# SwBotMain.net
KiCad netlist of a schematic drawn in EAGLE
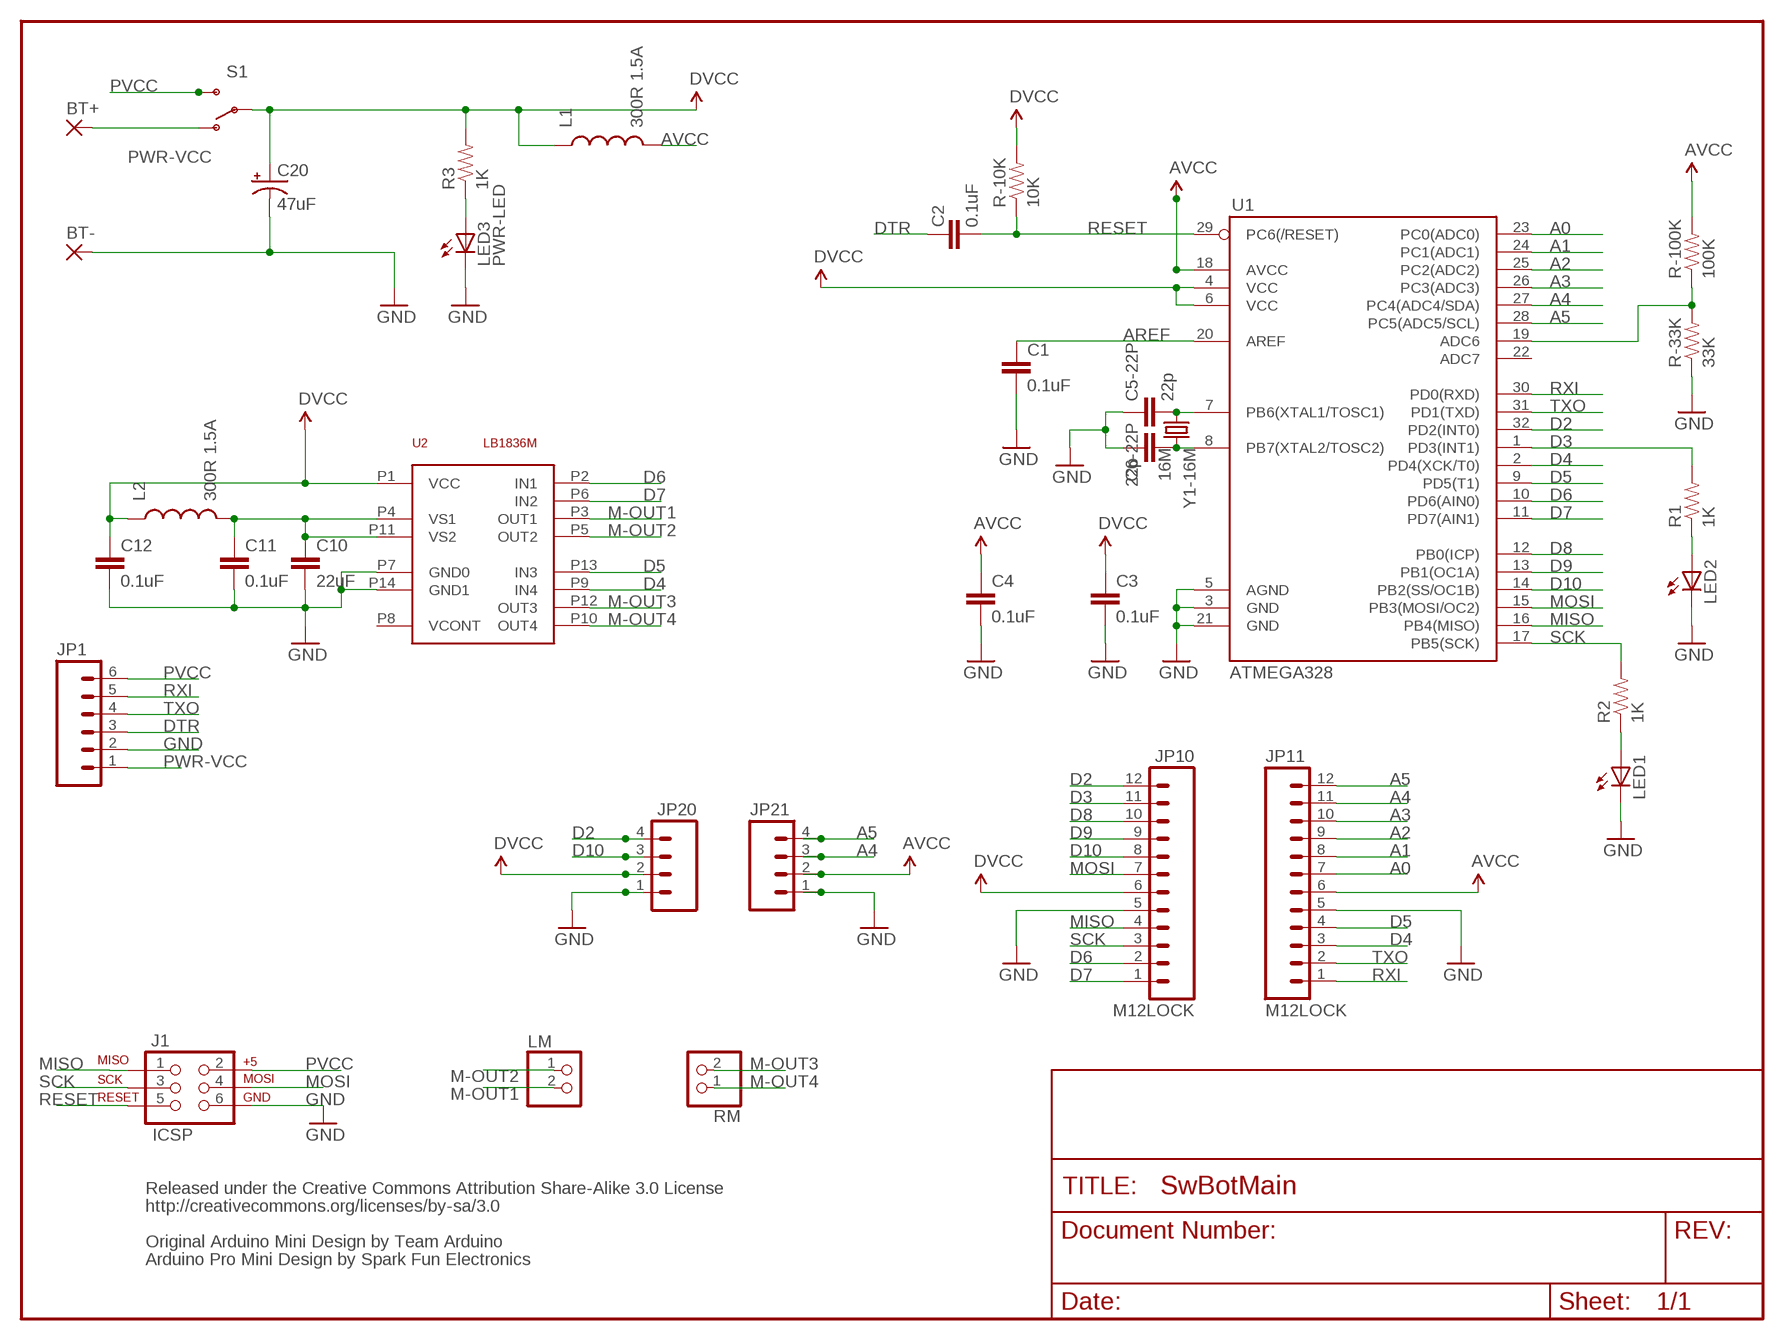
[diagram p0: schematic, sheet 1]

(export (version "E")
  (design (tool "Eeschema 10.0.6"))
  (components
    (comp (ref "BT+")
      (value "SMD2")
      (footprint "eagle-import:SMD1,27-2,54")
      (libsource (lib "eagle-import") (part "SMD2"))
    )
    (comp (ref "BT-")
      (value "SMD2")
      (footprint "eagle-import:SMD1,27-2,54")
      (libsource (lib "eagle-import") (part "SMD2"))
    )
    (comp (ref "C1")
      (value "0.1uF")
      (footprint "eagle-import:0805")
      (libsource (lib "eagle-import") (part "SparkFun-Capacitors_CAP0805"))
    )
    (comp (ref "C2")
      (value "0.1uF")
      (footprint "eagle-import:0805")
      (libsource (lib "eagle-import") (part "CAP0805"))
    )
    (comp (ref "C3")
      (value "0.1uF")
      (footprint "eagle-import:0805")
      (libsource (lib "eagle-import") (part "SparkFun-Capacitors_CAP0805"))
    )
    (comp (ref "C4")
      (value "0.1uF")
      (footprint "eagle-import:0805")
      (libsource (lib "eagle-import") (part "SparkFun-Capacitors_CAP0805"))
    )
    (comp (ref "C5-22P")
      (value "22p")
      (footprint "eagle-import:0805")
      (libsource (lib "eagle-import") (part "SparkFun-Capacitors_CAP0805"))
    )
    (comp (ref "C6-22P")
      (value "22p")
      (footprint "eagle-import:0805")
      (libsource (lib "eagle-import") (part "SparkFun-Capacitors_CAP0805"))
    )
    (comp (ref "C10")
      (value "22uF")
      (footprint "eagle-import:1206")
      (libsource (lib "eagle-import") (part "CAP1206"))
    )
    (comp (ref "C11")
      (value "0.1uF")
      (footprint "eagle-import:0805")
      (libsource (lib "eagle-import") (part "SparkFun-Capacitors_CAP0805"))
    )
    (comp (ref "C12")
      (value "0.1uF")
      (footprint "eagle-import:0805")
      (libsource (lib "eagle-import") (part "SparkFun-Capacitors_CAP0805"))
    )
    (comp (ref "C20")
      (value "47uF")
      (footprint "eagle-import:EIA3528")
      (libsource (lib "eagle-import") (part "47UF-TANT"))
    )
    (comp (ref "J1")
      (value "ICSP")
      (footprint "eagle-import:2X3_LOCK")
      (libsource (lib "eagle-import") (part "AVR_SPI_PRG_62X3_LOCK"))
    )
    (comp (ref "JP1")
      (value "M06LOCK")
      (footprint "eagle-import:1X06_LOCK")
      (libsource (lib "eagle-import") (part "M06LOCK"))
    )
    (comp (ref "JP10")
      (value "M12LOCK")
      (footprint "eagle-import:1X12_LOCK")
      (libsource (lib "eagle-import") (part "M12LOCK"))
    )
    (comp (ref "JP11")
      (value "M12LOCK")
      (footprint "eagle-import:1X12_LOCK")
      (libsource (lib "eagle-import") (part "M12LOCK"))
    )
    (comp (ref "JP20")
      (value "M04LOCK_LONGPADS")
      (footprint "eagle-import:1X04_LOCK_LONGPADS")
      (libsource (lib "eagle-import") (part "M04LOCK_LONGPADS"))
    )
    (comp (ref "JP21")
      (value "M04LOCK_LONGPADS")
      (footprint "eagle-import:1X04_LOCK_LONGPADS")
      (libsource (lib "eagle-import") (part "M04LOCK_LONGPADS"))
    )
    (comp (ref "L1")
      (value "300R 1.5A")
      (footprint "eagle-import:0805")
      (libsource (lib "eagle-import") (part "INDUCTOR0805"))
    )
    (comp (ref "L2")
      (value "300R 1.5A")
      (footprint "eagle-import:0805")
      (libsource (lib "eagle-import") (part "INDUCTOR0805"))
    )
    (comp (ref "LED1")
      (value "LEDCHIP-LED0805")
      (footprint "eagle-import:CHIP-LED0805")
      (libsource (lib "eagle-import") (part "LEDCHIP-LED0805"))
    )
    (comp (ref "LED2")
      (value "LEDCHIP-LED0805")
      (footprint "eagle-import:CHIP-LED0805")
      (libsource (lib "eagle-import") (part "LEDCHIP-LED0805"))
    )
    (comp (ref "LED3")
      (value "PWR-LED")
      (footprint "eagle-import:LED5MM")
      (libsource (lib "eagle-import") (part "LED5MM"))
    )
    (comp (ref "LM")
      (value "PINHD-1X2")
      (footprint "eagle-import:1X02")
      (libsource (lib "eagle-import") (part "PINHD-1X2"))
    )
    (comp (ref "R-10K")
      (value "10K")
      (footprint "eagle-import:0805")
      (libsource (lib "eagle-import") (part "RESISTOR0805-RES"))
    )
    (comp (ref "R-33K")
      (value "33K")
      (footprint "eagle-import:0805")
      (libsource (lib "eagle-import") (part "RESISTOR0805-RES"))
    )
    (comp (ref "R-100K")
      (value "100K")
      (footprint "eagle-import:0805")
      (libsource (lib "eagle-import") (part "RESISTOR0805-RES"))
    )
    (comp (ref "R1")
      (value "1K")
      (footprint "eagle-import:0805")
      (libsource (lib "eagle-import") (part "RESISTOR0805-RES"))
    )
    (comp (ref "R2")
      (value "1K")
      (footprint "eagle-import:0805")
      (libsource (lib "eagle-import") (part "RESISTOR0805-RES"))
    )
    (comp (ref "R3")
      (value "1K")
      (footprint "eagle-import:0805")
      (libsource (lib "eagle-import") (part "RESISTOR0805-RES"))
    )
    (comp (ref "RM")
      (value "PINHD-1X2")
      (footprint "eagle-import:1X02")
      (libsource (lib "eagle-import") (part "PINHD-1X2"))
    )
    (comp (ref "S1")
      (value "SWITCH-SPDTPTH_LOCK")
      (footprint "eagle-import:SWITCH-SPDT_LOCK.007S")
      (libsource (lib "eagle-import") (part "SWITCH-SPDTPTH_LOCK"))
    )
    (comp (ref "U1")
      (value "ATMEGA328")
      (footprint "eagle-import:TQFP32-08")
      (libsource (lib "eagle-import") (part "ATMEGA168"))
    )
    (comp (ref "U2")
      (value "LB1836M")
      (footprint "eagle-import:MFP14S")
      (libsource (lib "eagle-import") (part "LB1836M"))
    )
    (comp (ref "Y1-16M")
      (value "16M")
      (footprint "eagle-import:CRYSTAL-TXC-7A")
      (libsource (lib "eagle-import") (part "CRYSTALTXC-7A"))
    )
  )
  (nets
    (net (code "1") (name "/A0") (class "Default")
      (node (ref "JP11") (pin "7") (pinfunction "7_7") (pintype "passive"))
      (node (ref "U1") (pin "23") (pinfunction "PC0(ADC0)_23") (pintype "bidirectional"))
    )
    (net (code "2") (name "/A1") (class "Default")
      (node (ref "JP11") (pin "8") (pinfunction "8_8") (pintype "passive"))
      (node (ref "U1") (pin "24") (pinfunction "PC1(ADC1)_24") (pintype "bidirectional"))
    )
    (net (code "3") (name "/A2") (class "Default")
      (node (ref "JP11") (pin "9") (pinfunction "9_9") (pintype "passive"))
      (node (ref "U1") (pin "25") (pinfunction "PC2(ADC2)_25") (pintype "bidirectional"))
    )
    (net (code "4") (name "/A3") (class "Default")
      (node (ref "JP11") (pin "10") (pinfunction "10_10") (pintype "passive"))
      (node (ref "U1") (pin "26") (pinfunction "PC3(ADC3)_26") (pintype "bidirectional"))
    )
    (net (code "5") (name "/A4") (class "Default")
      (node (ref "JP11") (pin "11") (pinfunction "11_11") (pintype "passive"))
      (node (ref "JP21") (pin "3") (pinfunction "3_3") (pintype "passive"))
      (node (ref "U1") (pin "27") (pinfunction "PC4(ADC4/SDA)_27") (pintype "bidirectional"))
    )
    (net (code "6") (name "/A5") (class "Default")
      (node (ref "JP11") (pin "12") (pinfunction "12_12") (pintype "passive"))
      (node (ref "JP21") (pin "4") (pinfunction "4_4") (pintype "passive"))
      (node (ref "U1") (pin "28") (pinfunction "PC5(ADC5/SCL)_28") (pintype "bidirectional"))
    )
    (net (code "7") (name "/AREF") (class "Default")
      (node (ref "C1") (pin "1") (pinfunction "1_1") (pintype "passive"))
      (node (ref "U1") (pin "20") (pinfunction "AREF_20") (pintype "bidirectional"))
    )
    (net (code "8") (name "/D2") (class "Default")
      (node (ref "JP10") (pin "12") (pinfunction "12_12") (pintype "passive"))
      (node (ref "JP20") (pin "4") (pinfunction "4_4") (pintype "passive"))
      (node (ref "U1") (pin "32") (pinfunction "PD2(INT0)_32") (pintype "bidirectional"))
    )
    (net (code "9") (name "/D3") (class "Default")
      (node (ref "JP10") (pin "11") (pinfunction "11_11") (pintype "passive"))
      (node (ref "R1") (pin "2") (pinfunction "2_2") (pintype "passive"))
      (node (ref "U1") (pin "1") (pinfunction "PD3(INT1)_1") (pintype "bidirectional"))
    )
    (net (code "10") (name "/D4") (class "Default")
      (node (ref "JP11") (pin "3") (pinfunction "3_3") (pintype "passive"))
      (node (ref "U1") (pin "2") (pinfunction "PD4(XCK/T0)_2") (pintype "bidirectional"))
      (node (ref "U2") (pin "P9") (pinfunction "IN4_P9") (pintype "input"))
    )
    (net (code "11") (name "/D5") (class "Default")
      (node (ref "JP11") (pin "4") (pinfunction "4_4") (pintype "passive"))
      (node (ref "U1") (pin "9") (pinfunction "PD5(T1)_9") (pintype "bidirectional"))
      (node (ref "U2") (pin "P13") (pinfunction "IN3_P13") (pintype "input"))
    )
    (net (code "12") (name "/D6") (class "Default")
      (node (ref "JP10") (pin "2") (pinfunction "2_2") (pintype "passive"))
      (node (ref "U1") (pin "10") (pinfunction "PD6(AIN0)_10") (pintype "bidirectional"))
      (node (ref "U2") (pin "P2") (pinfunction "IN1_P2") (pintype "input"))
    )
    (net (code "13") (name "/D7") (class "Default")
      (node (ref "JP10") (pin "1") (pinfunction "1_1") (pintype "passive"))
      (node (ref "U1") (pin "11") (pinfunction "PD7(AIN1)_11") (pintype "bidirectional"))
      (node (ref "U2") (pin "P6") (pinfunction "IN2_P6") (pintype "input"))
    )
    (net (code "14") (name "/D8") (class "Default")
      (node (ref "JP10") (pin "10") (pinfunction "10_10") (pintype "passive"))
      (node (ref "U1") (pin "12") (pinfunction "PB0(ICP)_12") (pintype "bidirectional"))
    )
    (net (code "15") (name "/D9") (class "Default")
      (node (ref "JP10") (pin "9") (pinfunction "9_9") (pintype "passive"))
      (node (ref "U1") (pin "13") (pinfunction "PB1(OC1A)_13") (pintype "bidirectional"))
    )
    (net (code "16") (name "/D10") (class "Default")
      (node (ref "JP10") (pin "8") (pinfunction "8_8") (pintype "passive"))
      (node (ref "JP20") (pin "3") (pinfunction "3_3") (pintype "passive"))
      (node (ref "U1") (pin "14") (pinfunction "PB2(SS/OC1B)_14") (pintype "bidirectional"))
    )
    (net (code "17") (name "/DTR") (class "Default")
      (node (ref "C2") (pin "2") (pinfunction "2_2") (pintype "passive"))
      (node (ref "JP1") (pin "3") (pinfunction "3_3") (pintype "passive"))
    )
    (net (code "18") (name "/M-OUT1") (class "Default")
      (node (ref "LM") (pin "2") (pinfunction "2_2") (pintype "passive"))
      (node (ref "U2") (pin "P3") (pinfunction "OUT1_P3") (pintype "output"))
    )
    (net (code "19") (name "/M-OUT2") (class "Default")
      (node (ref "LM") (pin "1") (pinfunction "1_1") (pintype "passive"))
      (node (ref "U2") (pin "P5") (pinfunction "OUT2_P5") (pintype "output"))
    )
    (net (code "20") (name "/M-OUT3") (class "Default")
      (node (ref "RM") (pin "2") (pinfunction "2_2") (pintype "passive"))
      (node (ref "U2") (pin "P12") (pinfunction "OUT3_P12") (pintype "output"))
    )
    (net (code "21") (name "/M-OUT4") (class "Default")
      (node (ref "RM") (pin "1") (pinfunction "1_1") (pintype "passive"))
      (node (ref "U2") (pin "P10") (pinfunction "OUT4_P10") (pintype "output"))
    )
    (net (code "22") (name "/MISO") (class "Default")
      (node (ref "J1") (pin "1") (pinfunction "1_1") (pintype "passive"))
      (node (ref "JP10") (pin "4") (pinfunction "4_4") (pintype "passive"))
      (node (ref "U1") (pin "16") (pinfunction "PB4(MISO)_16") (pintype "bidirectional"))
    )
    (net (code "23") (name "/MOSI") (class "Default")
      (node (ref "J1") (pin "4") (pinfunction "4_4") (pintype "passive"))
      (node (ref "JP10") (pin "7") (pinfunction "7_7") (pintype "passive"))
      (node (ref "U1") (pin "15") (pinfunction "PB3(MOSI/OC2)_15") (pintype "bidirectional"))
    )
    (net (code "24") (name "/PVCC") (class "Default")
      (node (ref "J1") (pin "2") (pinfunction "2_2") (pintype "passive"))
      (node (ref "JP1") (pin "6") (pinfunction "6_6") (pintype "passive"))
      (node (ref "S1") (pin "3") (pinfunction "S_3") (pintype "passive"))
    )
    (net (code "25") (name "/PWR-VCC") (class "Default")
      (node (ref "BT+") (pin "1") (pinfunction "P_1") (pintype "passive"))
      (node (ref "JP1") (pin "1") (pinfunction "1_1") (pintype "passive"))
      (node (ref "S1") (pin "1") (pinfunction "O_1") (pintype "passive"))
    )
    (net (code "26") (name "/RESET") (class "Default")
      (node (ref "C2") (pin "1") (pinfunction "1_1") (pintype "passive"))
      (node (ref "J1") (pin "5") (pinfunction "5_5") (pintype "passive"))
      (node (ref "R-10K") (pin "1") (pinfunction "1_1") (pintype "passive"))
      (node (ref "U1") (pin "29") (pinfunction "PC6(/RESET)_29") (pintype "bidirectional"))
    )
    (net (code "27") (name "/RXI") (class "Default")
      (node (ref "JP1") (pin "5") (pinfunction "5_5") (pintype "passive"))
      (node (ref "JP11") (pin "1") (pinfunction "1_1") (pintype "passive"))
      (node (ref "U1") (pin "30") (pinfunction "PD0(RXD)_30") (pintype "bidirectional"))
    )
    (net (code "28") (name "/SCK") (class "Default")
      (node (ref "J1") (pin "3") (pinfunction "3_3") (pintype "passive"))
      (node (ref "JP10") (pin "3") (pinfunction "3_3") (pintype "passive"))
      (node (ref "R2") (pin "2") (pinfunction "2_2") (pintype "passive"))
      (node (ref "U1") (pin "17") (pinfunction "PB5(SCK)_17") (pintype "bidirectional"))
    )
    (net (code "29") (name "/TXO") (class "Default")
      (node (ref "JP1") (pin "4") (pinfunction "4_4") (pintype "passive"))
      (node (ref "JP11") (pin "2") (pinfunction "2_2") (pintype "passive"))
      (node (ref "U1") (pin "31") (pinfunction "PD1(TXD)_31") (pintype "bidirectional"))
    )
    (net (code "30") (name "AVCC") (class "Default")
      (node (ref "C4") (pin "1") (pinfunction "1_1") (pintype "passive"))
      (node (ref "JP11") (pin "6") (pinfunction "6_6") (pintype "passive"))
      (node (ref "JP21") (pin "2") (pinfunction "2_2") (pintype "passive"))
      (node (ref "L1") (pin "2") (pinfunction "2_2") (pintype "passive"))
      (node (ref "R-100K") (pin "2") (pinfunction "2_2") (pintype "passive"))
      (node (ref "U1") (pin "18") (pinfunction "AVCC_18") (pintype "bidirectional"))
    )
    (net (code "31") (name "DVCC") (class "Default")
      (node (ref "C12") (pin "1") (pinfunction "1_1") (pintype "passive"))
      (node (ref "C20") (pin "A") (pinfunction "+_A") (pintype "passive"))
      (node (ref "C3") (pin "1") (pinfunction "1_1") (pintype "passive"))
      (node (ref "JP10") (pin "6") (pinfunction "6_6") (pintype "passive"))
      (node (ref "JP20") (pin "2") (pinfunction "2_2") (pintype "passive"))
      (node (ref "L1") (pin "1") (pinfunction "1_1") (pintype "passive"))
      (node (ref "L2") (pin "1") (pinfunction "1_1") (pintype "passive"))
      (node (ref "R-10K") (pin "2") (pinfunction "2_2") (pintype "passive"))
      (node (ref "R3") (pin "2") (pinfunction "2_2") (pintype "passive"))
      (node (ref "S1") (pin "2") (pinfunction "P_2") (pintype "passive"))
      (node (ref "U1") (pin "4") (pinfunction "VCC_4") (pintype "bidirectional"))
      (node (ref "U1") (pin "6") (pinfunction "VCC_6") (pintype "bidirectional"))
      (node (ref "U2") (pin "P1") (pinfunction "VCC_P1") (pintype "power_in"))
    )
    (net (code "32") (name "GND") (class "Default")
      (node (ref "BT-") (pin "1") (pinfunction "P_1") (pintype "passive"))
      (node (ref "C1") (pin "2") (pinfunction "2_2") (pintype "passive"))
      (node (ref "C10") (pin "2") (pinfunction "2_2") (pintype "passive"))
      (node (ref "C11") (pin "2") (pinfunction "2_2") (pintype "passive"))
      (node (ref "C12") (pin "2") (pinfunction "2_2") (pintype "passive"))
      (node (ref "C20") (pin "C") (pinfunction "-_C") (pintype "passive"))
      (node (ref "C3") (pin "2") (pinfunction "2_2") (pintype "passive"))
      (node (ref "C4") (pin "2") (pinfunction "2_2") (pintype "passive"))
      (node (ref "C5-22P") (pin "1") (pinfunction "1_1") (pintype "passive"))
      (node (ref "C6-22P") (pin "2") (pinfunction "2_2") (pintype "passive"))
      (node (ref "J1") (pin "6") (pinfunction "6_6") (pintype "passive"))
      (node (ref "JP1") (pin "2") (pinfunction "2_2") (pintype "passive"))
      (node (ref "JP10") (pin "5") (pinfunction "5_5") (pintype "passive"))
      (node (ref "JP11") (pin "5") (pinfunction "5_5") (pintype "passive"))
      (node (ref "JP20") (pin "1") (pinfunction "1_1") (pintype "passive"))
      (node (ref "JP21") (pin "1") (pinfunction "1_1") (pintype "passive"))
      (node (ref "LED1") (pin "C") (pinfunction "C_C") (pintype "passive"))
      (node (ref "LED2") (pin "C") (pinfunction "C_C") (pintype "passive"))
      (node (ref "LED3") (pin "K") (pinfunction "C_K") (pintype "passive"))
      (node (ref "R-33K") (pin "1") (pinfunction "1_1") (pintype "passive"))
      (node (ref "U1") (pin "21") (pinfunction "GND_21") (pintype "bidirectional"))
      (node (ref "U1") (pin "3") (pinfunction "GND_3") (pintype "bidirectional"))
      (node (ref "U1") (pin "5") (pinfunction "AGND_5") (pintype "bidirectional"))
      (node (ref "U2") (pin "P14") (pinfunction "GND1_P14") (pintype "power_in"))
      (node (ref "U2") (pin "P7") (pinfunction "GND0_P7") (pintype "power_in"))
    )
    (net (code "33") (name "Net-(LED1-PadA)") (class "Default")
      (node (ref "LED1") (pin "A") (pinfunction "A_A") (pintype "passive"))
      (node (ref "R2") (pin "1") (pinfunction "1_1") (pintype "passive"))
    )
    (net (code "34") (name "Net-(LED2-PadA)") (class "Default")
      (node (ref "LED2") (pin "A") (pinfunction "A_A") (pintype "passive"))
      (node (ref "R1") (pin "1") (pinfunction "1_1") (pintype "passive"))
    )
    (net (code "35") (name "Net-(LED3-PadA)") (class "Default")
      (node (ref "LED3") (pin "A") (pinfunction "A_A") (pintype "passive"))
      (node (ref "R3") (pin "1") (pinfunction "1_1") (pintype "passive"))
    )
    (net (code "36") (name "Net-(U1-ADC6)") (class "Default")
      (node (ref "R-100K") (pin "1") (pinfunction "1_1") (pintype "passive"))
      (node (ref "R-33K") (pin "2") (pinfunction "2_2") (pintype "passive"))
      (node (ref "U1") (pin "19") (pinfunction "ADC6_19") (pintype "bidirectional"))
    )
    (net (code "37") (name "Net-(U1-PB6(XTAL1{slash}TOSC1))") (class "Default")
      (node (ref "C5-22P") (pin "2") (pinfunction "2_2") (pintype "passive"))
      (node (ref "U1") (pin "7") (pinfunction "PB6(XTAL1/TOSC1)_7") (pintype "bidirectional"))
      (node (ref "Y1-16M") (pin "P$1") (pinfunction "1_P$1") (pintype "passive"))
    )
    (net (code "38") (name "Net-(U1-PB7(XTAL2{slash}TOSC2))") (class "Default")
      (node (ref "C6-22P") (pin "1") (pinfunction "1_1") (pintype "passive"))
      (node (ref "U1") (pin "8") (pinfunction "PB7(XTAL2/TOSC2)_8") (pintype "bidirectional"))
      (node (ref "Y1-16M") (pin "P$2") (pinfunction "2_P$2") (pintype "passive"))
    )
    (net (code "39") (name "Net-(U2-VS1)") (class "Default")
      (node (ref "C10") (pin "1") (pinfunction "1_1") (pintype "passive"))
      (node (ref "C11") (pin "1") (pinfunction "1_1") (pintype "passive"))
      (node (ref "L2") (pin "2") (pinfunction "2_2") (pintype "passive"))
      (node (ref "U2") (pin "P11") (pinfunction "VS2_P11") (pintype "power_in"))
      (node (ref "U2") (pin "P4") (pinfunction "VS1_P4") (pintype "power_in"))
    )
    (net (code "40") (name "unconnected-(U1-ADC7-Pad22)") (class "Default")
      (node (ref "U1") (pin "22") (pinfunction "ADC7_22") (pintype "bidirectional"))
    )
    (net (code "41") (name "unconnected-(U2-VCONT-PadP8)") (class "Default")
      (node (ref "U2") (pin "P8") (pinfunction "VCONT_P8") (pintype "output"))
    )
  )
)
